# XS128.net
KiCad netlist of a schematic drawn in Altium Designer
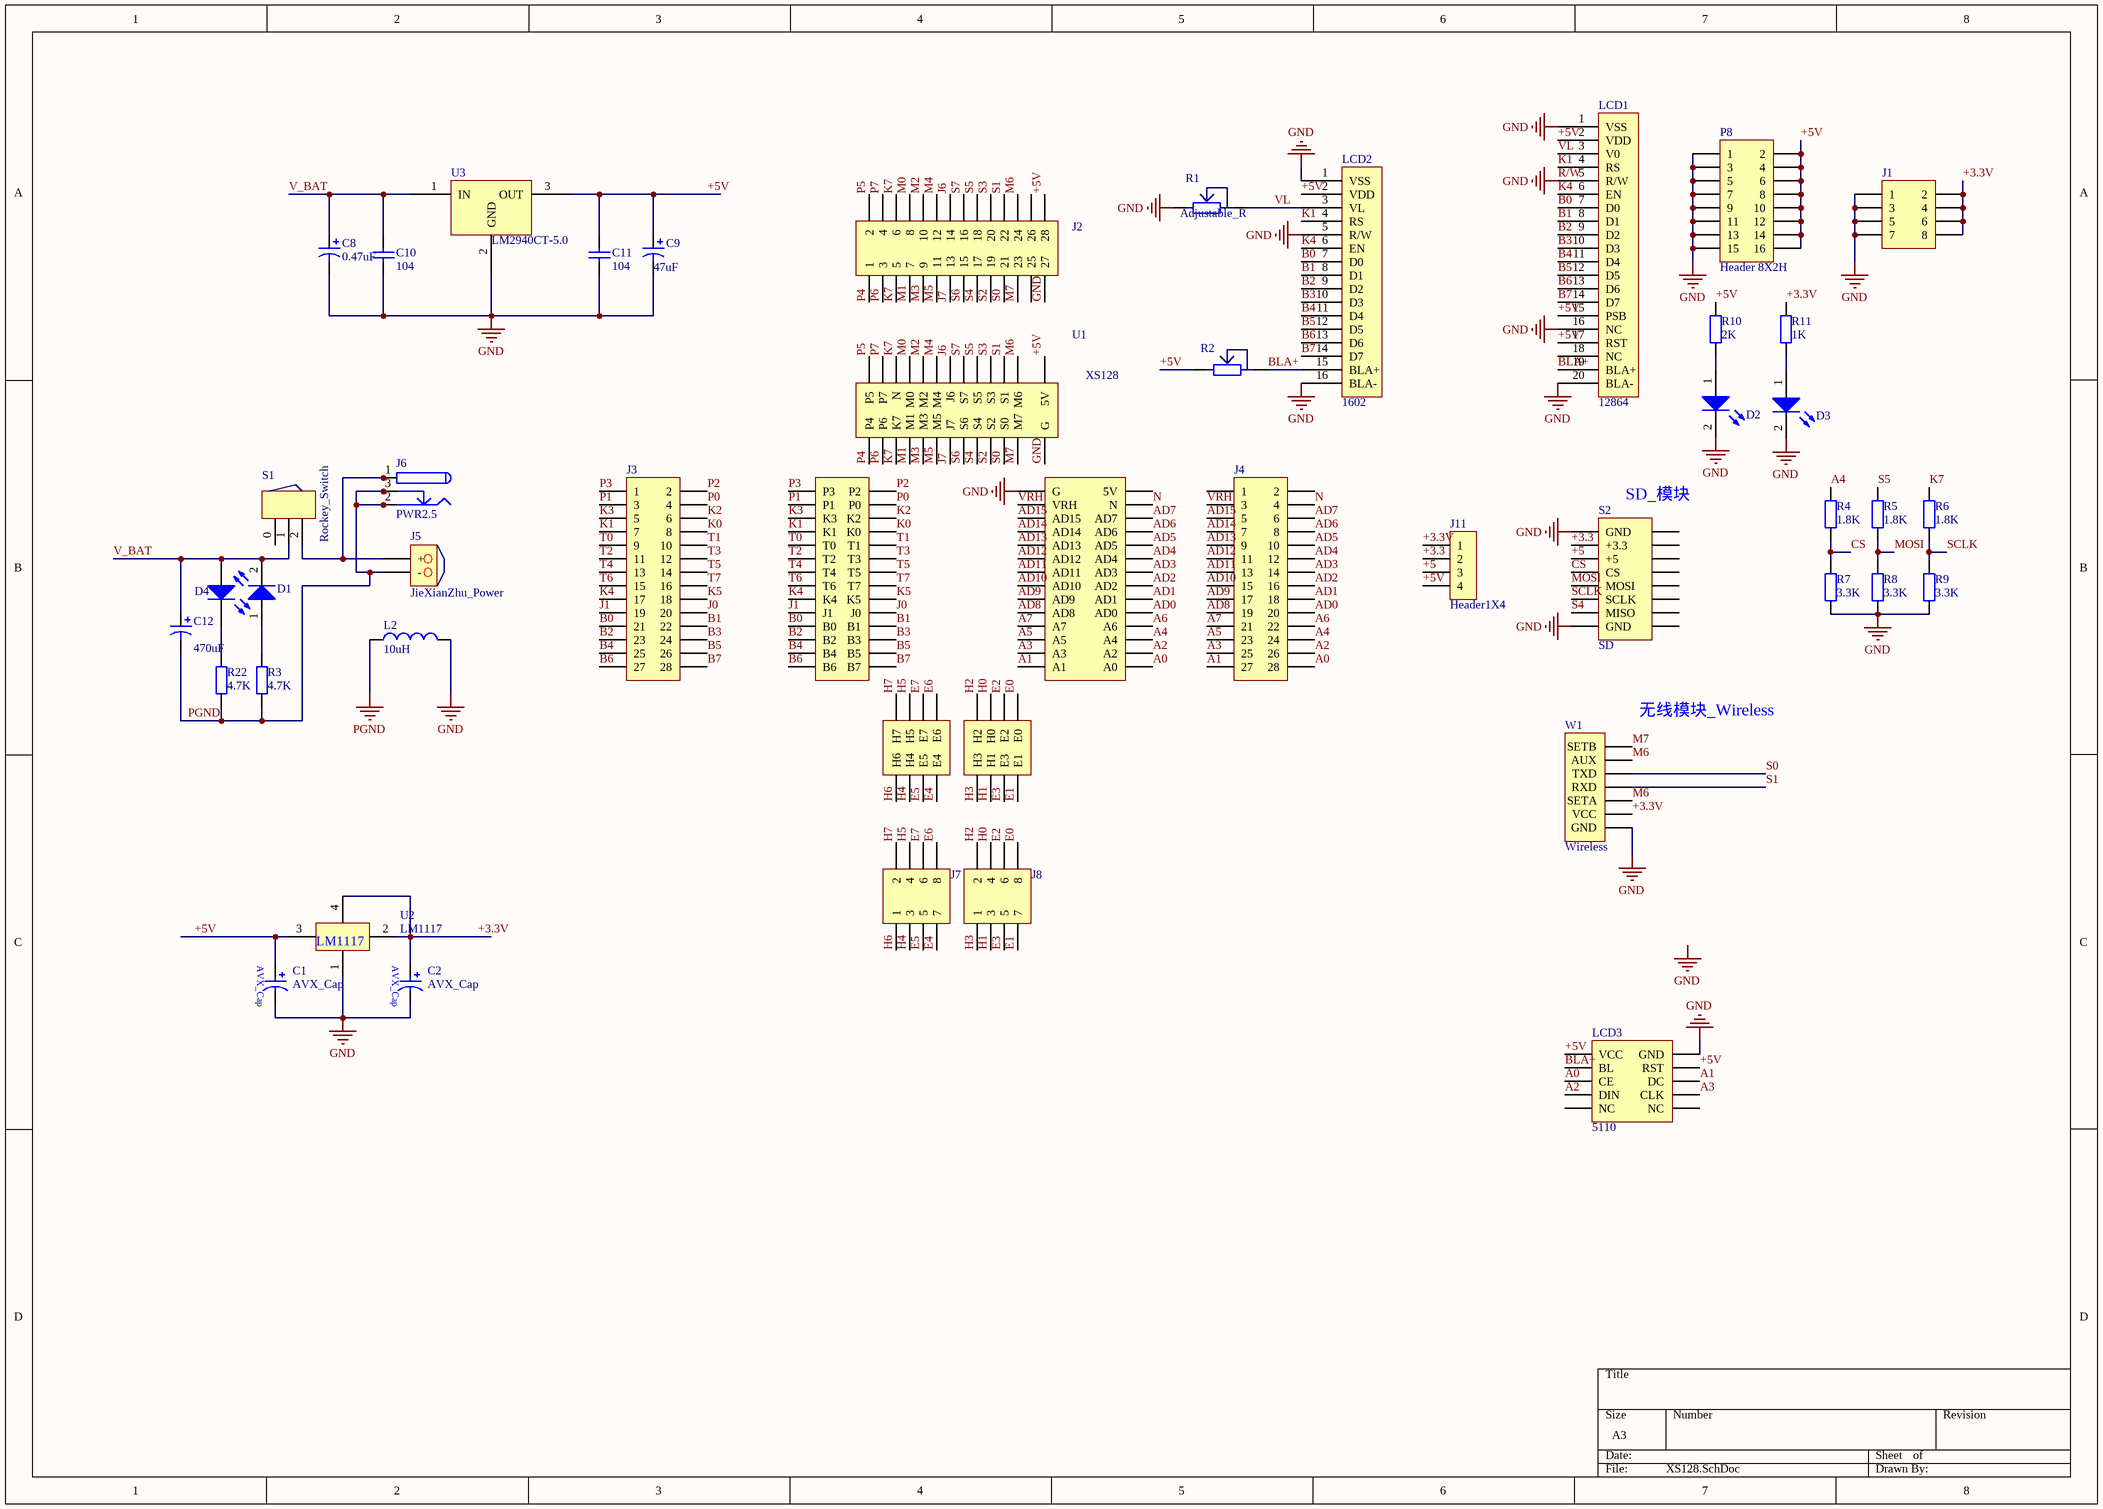
[diagram p0: XS128.SchDoc]

(export (version "E")
  (design (tool "Eeschema 10.0.6"))
  (components
    (comp (ref "C1") (value "AVX_Cap") (footprint "AVX_Cap_10uF") (libsource (lib "*") (part "AVX_Cap")))
    (comp (ref "C2") (value "AVX_Cap") (footprint "AVX_Cap_10uF") (libsource (lib "*") (part "AVX_Cap")))
    (comp (ref "C8")
      (value "0.47uF")
      (footprint "0.47UF/50V")
      (description "Polarized Capacitor (Surface Mount)")
      (fields (field (name "Comment") "Cap Pol3") (field (name "PUBLISHER") "Altium Limited"))
      (libsource (lib "元件库") (part "Cap Pol3"))
    )
    (comp (ref "C9")
      (value "47uF")
      (footprint "47uf/25V")
      (description "Polarized Capacitor (Surface Mount)")
      (fields (field (name "Comment") "Cap Pol3") (field (name "PUBLISHER") "Altium Limited"))
      (libsource (lib "元件库") (part "Cap Pol3"))
    )
    (comp (ref "C10")
      (value "104")
      (footprint "6-0805")
      (description "Capacitor")
      (fields (field (name "Comment") "Cap") (field (name "PUBLISHER") "Altium Limited"))
      (libsource (lib "元件库") (part "Cap"))
    )
    (comp (ref "C11")
      (value "104")
      (footprint "6-0805")
      (description "Capacitor")
      (fields (field (name "Comment") "Cap") (field (name "PUBLISHER") "Altium Limited"))
      (libsource (lib "元件库") (part "Cap"))
    )
    (comp (ref "C12")
      (value "470uF")
      (footprint "470uF/25V")
      (description "Polarized Capacitor (Radial)")
      (fields (field (name "Comment") "Cap Pol1") (field (name "PUBLISHER") "Altium Limited"))
      (libsource (lib "Miscellaneous Devices") (part "Cap Pol1"))
    )
    (comp (ref "D1")
      (value "LED1")
      (footprint "0805电阻贴片")
      (description "RED_LED")
      (fields (field (name "PUBLISHER") "Altium Limited"))
      (libsource (lib "") (part "LED1_1"))
    )
    (comp (ref "D2")
      (value "LED1")
      (footprint "0805电阻贴片")
      (description "RED_LED")
      (fields (field (name "PUBLISHER") "Altium Limited"))
      (libsource (lib "我的XS128集成库") (part "LED1"))
    )
    (comp (ref "D3")
      (value "LED1")
      (footprint "0805电阻贴片")
      (description "RED_LED")
      (fields (field (name "PUBLISHER") "Altium Limited"))
      (libsource (lib "我的XS128集成库") (part "LED1"))
    )
    (comp (ref "D4")
      (value "LED1")
      (footprint "3.2X1.6X1.1")
      (description "Typical RED GaAs LED")
      (fields (field (name "PUBLISHER") "Altium Limited"))
      (libsource (lib "Miscellaneous Devices") (part "LED1"))
    )
    (comp (ref "J1")
      (value "Header 4X2")
      (footprint "HDR2X4")
      (description "Header, 4-Pin, Dual row")
      (fields (field (name "PUBLISHER") "Altium Limited"))
      (libsource (lib "") (part "Header 4X2_1"))
    )
    (comp (ref "J2")
      (value "Header 14X2")
      (footprint "HDR2X14")
      (description "Header, 14-Pin, Dual row")
      (fields (field (name "PUBLISHER") "Altium Limited"))
      (libsource (lib "Miscellaneous Connectors") (part "Header 14X2"))
    )
    (comp (ref "J3")
      (value "Header 14X2")
      (footprint "HDR2X14")
      (description "Header, 14-Pin, Dual row")
      (fields (field (name "PUBLISHER") "Altium Limited"))
      (libsource (lib "") (part "Header 14X2_1"))
    )
    (comp (ref "J4")
      (value "Header 14X2")
      (footprint "HDR2X14")
      (description "Header, 14-Pin, Dual row")
      (fields (field (name "PUBLISHER") "Altium Limited"))
      (libsource (lib "") (part "Header 14X2_1"))
    )
    (comp (ref "J5")
      (value "JieXianZhu_Power")
      (footprint "jiexianzhu_power")
      (libsource (lib "*") (part "JieXianZhu_Power"))
    )
    (comp (ref "J6")
      (value "PWR2.5")
      (footprint "KLD-0202")
      (description "Low Voltage Power Supply Connector")
      (fields (field (name "PUBLISHER") "Altium Limited"))
      (libsource (lib "Miscellaneous Connectors") (part "PWR2.5"))
    )
    (comp (ref "J7")
      (value "Header 4X2")
      (footprint "HDR2X4")
      (description "Header, 4-Pin, Dual row")
      (fields (field (name "PUBLISHER") "Altium Limited"))
      (libsource (lib "Miscellaneous Connectors") (part "Header 4X2"))
    )
    (comp (ref "J8")
      (value "Header 4X2")
      (footprint "HDR2X4")
      (description "Header, 4-Pin, Dual row")
      (fields (field (name "PUBLISHER") "Altium Limited"))
      (libsource (lib "Miscellaneous Connectors") (part "Header 4X2"))
    )
    (comp (ref "J11") (value "Header1X4") (footprint "HDR1X4") (libsource (lib "*") (part "Header1X4")))
    (comp (ref "L2")
      (value "10uH")
      (footprint "INDUCTOR")
      (description "Inductor")
      (fields (field (name "PUBLISHER") "Altium Limited"))
      (libsource (lib "元件库") (part "Inductor"))
    )
    (comp (ref "LCD1") (value "12864") (footprint "HDR!X20") (libsource (lib "*") (part "12864")))
    (comp (ref "LCD2") (value "1602") (footprint "HDR1X16") (libsource (lib "*") (part "1602")))
    (comp (ref "LCD3") (value "5110") (footprint "5110") (libsource (lib "*") (part "5110")))
    (comp (ref "P8")
      (value "Header 8X2H")
      (footprint "HDR2X8H")
      (description "Header, 8-Pin, Dual row, Right Angle")
      (fields (field (name "PUBLISHER") "Altium Limited"))
      (libsource (lib "Miscellaneous Connectors") (part "Header 8X2H"))
    )
    (comp (ref "R1")
      (value "Adjustable_R")
      (footprint "Adjustable_R")
      (libsource (lib "*") (part "Adjustable_R"))
    )
    (comp (ref "R2")
      (value "Adjustable_R")
      (footprint "Adjustable_R")
      (libsource (lib "*") (part "Adjustable_R"))
    )
    (comp (ref "R3")
      (value "4.7K")
      (footprint "0805电阻贴片")
      (description "Resistor")
      (fields (field (name "Comment") "Res2") (field (name "PUBLISHER") "Altium Limited"))
      (libsource (lib "Miscellaneous Devices") (part "Res2"))
    )
    (comp (ref "R4")
      (value "1.8K")
      (footprint "0805电阻贴片")
      (description "Resistor")
      (fields (field (name "Comment") "Res2") (field (name "PUBLISHER") "Altium Limited"))
      (libsource (lib "我的XS128集成库") (part "Res2"))
    )
    (comp (ref "R5")
      (value "1.8K")
      (footprint "0805电阻贴片")
      (description "Resistor")
      (fields (field (name "Comment") "Res2") (field (name "PUBLISHER") "Altium Limited"))
      (libsource (lib "我的XS128集成库") (part "Res2"))
    )
    (comp (ref "R6")
      (value "1.8K")
      (footprint "0805电阻贴片")
      (description "Resistor")
      (fields (field (name "Comment") "Res2") (field (name "PUBLISHER") "Altium Limited"))
      (libsource (lib "我的XS128集成库") (part "Res2"))
    )
    (comp (ref "R7")
      (value "3.3K")
      (footprint "0805电阻贴片")
      (description "Resistor")
      (fields (field (name "Comment") "Res2") (field (name "PUBLISHER") "Altium Limited"))
      (libsource (lib "") (part "Res2_1"))
    )
    (comp (ref "R8")
      (value "3.3K")
      (footprint "0805电阻贴片")
      (description "Resistor")
      (fields (field (name "Comment") "Res2") (field (name "PUBLISHER") "Altium Limited"))
      (libsource (lib "") (part "Res2_1"))
    )
    (comp (ref "R9")
      (value "3.3K")
      (footprint "0805电阻贴片")
      (description "Resistor")
      (fields (field (name "Comment") "Res2") (field (name "PUBLISHER") "Altium Limited"))
      (libsource (lib "") (part "Res2_1"))
    )
    (comp (ref "R10")
      (value "2K")
      (footprint "0805电阻贴片")
      (description "Resistor")
      (fields (field (name "Comment") "Res2") (field (name "PUBLISHER") "Altium Limited"))
      (libsource (lib "我的XS128集成库") (part "Res2"))
    )
    (comp (ref "R11")
      (value "1K")
      (footprint "0805电阻贴片")
      (description "Resistor")
      (fields (field (name "Comment") "Res2") (field (name "PUBLISHER") "Altium Limited"))
      (libsource (lib "我的XS128集成库") (part "Res2"))
    )
    (comp (ref "R22")
      (value "4.7K")
      (footprint "2012[0805]")
      (description "Resistor")
      (fields (field (name "Comment") "Res2") (field (name "PUBLISHER") "Altium Limited"))
      (libsource (lib "Miscellaneous Devices") (part "Res2"))
    )
    (comp (ref "S1")
      (value "Rockey_Switch")
      (footprint "Rockey_Switch")
      (libsource (lib "*") (part "Rockey_Switch"))
    )
    (comp (ref "S2") (value "SD") (footprint "SD") (libsource (lib "*") (part "SD")))
    (comp (ref "U1") (value "XS128") (footprint "XS128接口") (libsource (lib "元件库") (part "XS128")))
    (comp (ref "U2") (value "LM1117") (footprint "SOT230LM1117") (libsource (lib "*") (part "LM1117")))
    (comp (ref "U3")
      (value "LM2940CT-5.0")
      (footprint "LM2940")
      (libsource (lib "元件库") (part "LM2940CT-5.0"))
    )
    (comp (ref "W1") (value "Wireless") (footprint "WIRELESS") (libsource (lib "*") (part "Wireless")))
  )
  (nets
    (net (code "1") (name "/+3.3") (class "Default")
      (node (ref "J11") (pin "2") (pinfunction "2_2") (pintype "passive"))
      (node (ref "S2") (pin "1") (pinfunction "+3.3_1") (pintype "passive"))
    )
    (net (code "2") (name "/+3.3V") (class "Default")
      (node (ref "C2") (pin "1") (pinfunction "+_1") (pintype "passive"))
      (node (ref "J1") (pin "2") (pinfunction "2_2") (pintype "passive"))
      (node (ref "J1") (pin "4") (pinfunction "4_4") (pintype "passive"))
      (node (ref "J1") (pin "6") (pinfunction "6_6") (pintype "passive"))
      (node (ref "J1") (pin "8") (pinfunction "8_8") (pintype "passive"))
      (node (ref "J11") (pin "1") (pinfunction "1_1") (pintype "passive"))
      (node (ref "R11") (pin "2") (pinfunction "2_2") (pintype "passive"))
      (node (ref "U2") (pin "2") (pinfunction "OUT_2") (pintype "passive"))
      (node (ref "U2") (pin "4") (pinfunction "TAB_4") (pintype "power_in"))
      (node (ref "W1") (pin "1") (pinfunction "VCC_1") (pintype "passive"))
    )
    (net (code "3") (name "/+5") (class "Default")
      (node (ref "J11") (pin "3") (pinfunction "3_3") (pintype "passive"))
      (node (ref "S2") (pin "2") (pinfunction "+5_2") (pintype "passive"))
    )
    (net (code "4") (name "/+5V") (class "Default")
      (node (ref "C1") (pin "1") (pinfunction "+_1") (pintype "passive"))
      (node (ref "C11") (pin "1") (pinfunction "1_1") (pintype "passive"))
      (node (ref "C9") (pin "1") (pinfunction "1_1") (pintype "passive"))
      (node (ref "J11") (pin "4") (pinfunction "4_4") (pintype "passive"))
      (node (ref "J2") (pin "28") (pinfunction "28_28") (pintype "passive"))
      (node (ref "LCD1") (pin "15") (pinfunction "PSB_15") (pintype "passive"))
      (node (ref "LCD1") (pin "17") (pinfunction "RST_17") (pintype "passive"))
      (node (ref "LCD1") (pin "2") (pinfunction "VDD_2") (pintype "passive"))
      (node (ref "LCD2") (pin "2") (pinfunction "VDD_2") (pintype "passive"))
      (node (ref "LCD3") (pin "0") (pinfunction "VCC_0") (pintype "passive"))
      (node (ref "LCD3") (pin "3") (pinfunction "RST_3") (pintype "passive"))
      (node (ref "P8") (pin "10") (pinfunction "10_10") (pintype "passive"))
      (node (ref "P8") (pin "12") (pinfunction "12_12") (pintype "passive"))
      (node (ref "P8") (pin "14") (pinfunction "14_14") (pintype "passive"))
      (node (ref "P8") (pin "16") (pinfunction "16_16") (pintype "passive"))
      (node (ref "P8") (pin "2") (pinfunction "2_2") (pintype "passive"))
      (node (ref "P8") (pin "4") (pinfunction "4_4") (pintype "passive"))
      (node (ref "P8") (pin "6") (pinfunction "6_6") (pintype "passive"))
      (node (ref "P8") (pin "8") (pinfunction "8_8") (pintype "passive"))
      (node (ref "R10") (pin "2") (pinfunction "2_2") (pintype "passive"))
      (node (ref "R2") (pin "1") (pinfunction "1_1") (pintype "passive"))
      (node (ref "U1") (pin "201") (pinfunction "5V_201") (pintype "passive"))
      (node (ref "U2") (pin "3") (pinfunction "IN_3") (pintype "passive"))
      (node (ref "U3") (pin "3") (pinfunction "OUT_3") (pintype "passive"))
    )
    (net (code "5") (name "/A0") (class "Default")
      (node (ref "J4") (pin "28") (pinfunction "28_28") (pintype "passive"))
      (node (ref "LCD3") (pin "4") (pinfunction "CE_4") (pintype "passive"))
      (node (ref "U1") (pin "301") (pinfunction "A0_301") (pintype "passive"))
    )
    (net (code "6") (name "/A1") (class "Default")
      (node (ref "J4") (pin "27") (pinfunction "27_27") (pintype "passive"))
      (node (ref "LCD3") (pin "5") (pinfunction "DC_5") (pintype "passive"))
      (node (ref "U1") (pin "302") (pinfunction "A1_302") (pintype "passive"))
    )
    (net (code "7") (name "/A2") (class "Default")
      (node (ref "J4") (pin "26") (pinfunction "26_26") (pintype "passive"))
      (node (ref "LCD3") (pin "6") (pinfunction "DIN_6") (pintype "passive"))
      (node (ref "U1") (pin "303") (pinfunction "A2_303") (pintype "passive"))
    )
    (net (code "8") (name "/A3") (class "Default")
      (node (ref "J4") (pin "25") (pinfunction "25_25") (pintype "passive"))
      (node (ref "LCD3") (pin "7") (pinfunction "CLK_7") (pintype "passive"))
      (node (ref "U1") (pin "304") (pinfunction "A3_304") (pintype "passive"))
    )
    (net (code "9") (name "/A4") (class "Default")
      (node (ref "J4") (pin "24") (pinfunction "24_24") (pintype "passive"))
      (node (ref "R4") (pin "2") (pinfunction "2_2") (pintype "passive"))
      (node (ref "U1") (pin "305") (pinfunction "A4_305") (pintype "passive"))
    )
    (net (code "10") (name "/A5") (class "Default")
      (node (ref "J4") (pin "23") (pinfunction "23_23") (pintype "passive"))
      (node (ref "U1") (pin "306") (pinfunction "A5_306") (pintype "passive"))
    )
    (net (code "11") (name "/A6") (class "Default")
      (node (ref "J4") (pin "22") (pinfunction "22_22") (pintype "passive"))
      (node (ref "U1") (pin "307") (pinfunction "A6_307") (pintype "passive"))
    )
    (net (code "12") (name "/A7") (class "Default")
      (node (ref "J4") (pin "21") (pinfunction "21_21") (pintype "passive"))
      (node (ref "U1") (pin "308") (pinfunction "A7_308") (pintype "passive"))
    )
    (net (code "13") (name "/AD0") (class "Default")
      (node (ref "J4") (pin "20") (pinfunction "20_20") (pintype "passive"))
      (node (ref "U1") (pin "309") (pinfunction "AD0_309") (pintype "passive"))
    )
    (net (code "14") (name "/AD1") (class "Default")
      (node (ref "J4") (pin "18") (pinfunction "18_18") (pintype "passive"))
      (node (ref "U1") (pin "311") (pinfunction "AD1_311") (pintype "passive"))
    )
    (net (code "15") (name "/AD2") (class "Default")
      (node (ref "J4") (pin "16") (pinfunction "16_16") (pintype "passive"))
      (node (ref "U1") (pin "313") (pinfunction "AD2_313") (pintype "passive"))
    )
    (net (code "16") (name "/AD3") (class "Default")
      (node (ref "J4") (pin "14") (pinfunction "14_14") (pintype "passive"))
      (node (ref "U1") (pin "315") (pinfunction "AD3_315") (pintype "passive"))
    )
    (net (code "17") (name "/AD4") (class "Default")
      (node (ref "J4") (pin "12") (pinfunction "12_12") (pintype "passive"))
      (node (ref "U1") (pin "317") (pinfunction "AD4_317") (pintype "passive"))
    )
    (net (code "18") (name "/AD5") (class "Default")
      (node (ref "J4") (pin "10") (pinfunction "10_10") (pintype "passive"))
      (node (ref "U1") (pin "319") (pinfunction "AD5_319") (pintype "passive"))
    )
    (net (code "19") (name "/AD6") (class "Default")
      (node (ref "J4") (pin "8") (pinfunction "8_8") (pintype "passive"))
      (node (ref "U1") (pin "321") (pinfunction "AD6_321") (pintype "passive"))
    )
    (net (code "20") (name "/AD7") (class "Default")
      (node (ref "J4") (pin "6") (pinfunction "6_6") (pintype "passive"))
      (node (ref "U1") (pin "323") (pinfunction "AD7_323") (pintype "passive"))
    )
    (net (code "21") (name "/AD8") (class "Default")
      (node (ref "J4") (pin "19") (pinfunction "19_19") (pintype "passive"))
      (node (ref "U1") (pin "310") (pinfunction "AD8_310") (pintype "passive"))
    )
    (net (code "22") (name "/AD9") (class "Default")
      (node (ref "J4") (pin "17") (pinfunction "17_17") (pintype "passive"))
      (node (ref "U1") (pin "312") (pinfunction "AD9_312") (pintype "passive"))
    )
    (net (code "23") (name "/AD10") (class "Default")
      (node (ref "J4") (pin "15") (pinfunction "15_15") (pintype "passive"))
      (node (ref "U1") (pin "314") (pinfunction "AD10_314") (pintype "passive"))
    )
    (net (code "24") (name "/AD11") (class "Default")
      (node (ref "J4") (pin "13") (pinfunction "13_13") (pintype "passive"))
      (node (ref "U1") (pin "316") (pinfunction "AD11_316") (pintype "passive"))
    )
    (net (code "25") (name "/AD12") (class "Default")
      (node (ref "J4") (pin "11") (pinfunction "11_11") (pintype "passive"))
      (node (ref "U1") (pin "318") (pinfunction "AD12_318") (pintype "passive"))
    )
    (net (code "26") (name "/AD13") (class "Default")
      (node (ref "J4") (pin "9") (pinfunction "9_9") (pintype "passive"))
      (node (ref "U1") (pin "320") (pinfunction "AD13_320") (pintype "passive"))
    )
    (net (code "27") (name "/AD14") (class "Default")
      (node (ref "J4") (pin "7") (pinfunction "7_7") (pintype "passive"))
      (node (ref "U1") (pin "322") (pinfunction "AD14_322") (pintype "passive"))
    )
    (net (code "28") (name "/AD15") (class "Default")
      (node (ref "J4") (pin "5") (pinfunction "5_5") (pintype "passive"))
      (node (ref "U1") (pin "324") (pinfunction "AD15_324") (pintype "passive"))
    )
    (net (code "29") (name "/B0") (class "Default")
      (node (ref "J3") (pin "21") (pinfunction "21_21") (pintype "passive"))
      (node (ref "LCD1") (pin "7") (pinfunction "D0_7") (pintype "passive"))
      (node (ref "LCD2") (pin "7") (pinfunction "D0_7") (pintype "passive"))
      (node (ref "U1") (pin "121") (pinfunction "B0_121") (pintype "passive"))
    )
    (net (code "30") (name "/B1") (class "Default")
      (node (ref "J3") (pin "22") (pinfunction "22_22") (pintype "passive"))
      (node (ref "LCD1") (pin "8") (pinfunction "D1_8") (pintype "passive"))
      (node (ref "LCD2") (pin "8") (pinfunction "D1_8") (pintype "passive"))
      (node (ref "U1") (pin "122") (pinfunction "B1_122") (pintype "passive"))
    )
    (net (code "31") (name "/B2") (class "Default")
      (node (ref "J3") (pin "23") (pinfunction "23_23") (pintype "passive"))
      (node (ref "LCD1") (pin "9") (pinfunction "D2_9") (pintype "passive"))
      (node (ref "LCD2") (pin "9") (pinfunction "D2_9") (pintype "passive"))
      (node (ref "U1") (pin "123") (pinfunction "B2_123") (pintype "passive"))
    )
    (net (code "32") (name "/B3") (class "Default")
      (node (ref "J3") (pin "24") (pinfunction "24_24") (pintype "passive"))
      (node (ref "LCD1") (pin "10") (pinfunction "D3_10") (pintype "passive"))
      (node (ref "LCD2") (pin "10") (pinfunction "D3_10") (pintype "passive"))
      (node (ref "U1") (pin "124") (pinfunction "B3_124") (pintype "passive"))
    )
    (net (code "33") (name "/B4") (class "Default")
      (node (ref "J3") (pin "25") (pinfunction "25_25") (pintype "passive"))
      (node (ref "LCD1") (pin "11") (pinfunction "D4_11") (pintype "passive"))
      (node (ref "LCD2") (pin "11") (pinfunction "D4_11") (pintype "passive"))
      (node (ref "U1") (pin "125") (pinfunction "B4_125") (pintype "passive"))
    )
    (net (code "34") (name "/B5") (class "Default")
      (node (ref "J3") (pin "26") (pinfunction "26_26") (pintype "passive"))
      (node (ref "LCD1") (pin "12") (pinfunction "D5_12") (pintype "passive"))
      (node (ref "LCD2") (pin "12") (pinfunction "D5_12") (pintype "passive"))
      (node (ref "U1") (pin "126") (pinfunction "B5_126") (pintype "passive"))
    )
    (net (code "35") (name "/B6") (class "Default")
      (node (ref "J3") (pin "27") (pinfunction "27_27") (pintype "passive"))
      (node (ref "LCD1") (pin "13") (pinfunction "D6_13") (pintype "passive"))
      (node (ref "LCD2") (pin "13") (pinfunction "D6_13") (pintype "passive"))
      (node (ref "U1") (pin "127") (pinfunction "B6_127") (pintype "passive"))
    )
    (net (code "36") (name "/B7") (class "Default")
      (node (ref "J3") (pin "28") (pinfunction "28_28") (pintype "passive"))
      (node (ref "LCD1") (pin "14") (pinfunction "D7_14") (pintype "passive"))
      (node (ref "LCD2") (pin "14") (pinfunction "D7_14") (pintype "passive"))
      (node (ref "U1") (pin "128") (pinfunction "B7_128") (pintype "passive"))
    )
    (net (code "37") (name "/BLA+") (class "Default")
      (node (ref "LCD1") (pin "19") (pinfunction "BLA+_19") (pintype "passive"))
      (node (ref "LCD2") (pin "15") (pinfunction "BLA+_15") (pintype "passive"))
      (node (ref "LCD3") (pin "2") (pinfunction "BL_2") (pintype "passive"))
      (node (ref "R2") (pin "2") (pinfunction "2_2") (pintype "passive"))
    )
    (net (code "38") (name "/CS") (class "Default")
      (node (ref "R4") (pin "1") (pinfunction "1_1") (pintype "passive"))
      (node (ref "R7") (pin "1") (pinfunction "1_1") (pintype "passive"))
      (node (ref "S2") (pin "3") (pinfunction "CS_3") (pintype "passive"))
    )
    (net (code "39") (name "/E0") (class "Default")
      (node (ref "J8") (pin "8") (pinfunction "8_8") (pintype "passive"))
      (node (ref "U1") (pin "508") (pinfunction "E0_508") (pintype "passive"))
    )
    (net (code "40") (name "/E1") (class "Default")
      (node (ref "J8") (pin "7") (pinfunction "7_7") (pintype "passive"))
      (node (ref "U1") (pin "507") (pinfunction "E1_507") (pintype "passive"))
    )
    (net (code "41") (name "/E2") (class "Default")
      (node (ref "J8") (pin "6") (pinfunction "6_6") (pintype "passive"))
      (node (ref "U1") (pin "506") (pinfunction "E2_506") (pintype "passive"))
    )
    (net (code "42") (name "/E3") (class "Default")
      (node (ref "J8") (pin "5") (pinfunction "5_5") (pintype "passive"))
      (node (ref "U1") (pin "505") (pinfunction "E3_505") (pintype "passive"))
    )
    (net (code "43") (name "/E4") (class "Default")
      (node (ref "J7") (pin "7") (pinfunction "7_7") (pintype "passive"))
      (node (ref "U1") (pin "407") (pinfunction "E4_407") (pintype "passive"))
    )
    (net (code "44") (name "/E5") (class "Default")
      (node (ref "J7") (pin "5") (pinfunction "5_5") (pintype "passive"))
      (node (ref "U1") (pin "405") (pinfunction "E5_405") (pintype "passive"))
    )
    (net (code "45") (name "/E6") (class "Default")
      (node (ref "J7") (pin "8") (pinfunction "8_8") (pintype "passive"))
      (node (ref "U1") (pin "408") (pinfunction "E6_408") (pintype "passive"))
    )
    (net (code "46") (name "/E7") (class "Default")
      (node (ref "J7") (pin "6") (pinfunction "6_6") (pintype "passive"))
      (node (ref "U1") (pin "406") (pinfunction "E7_406") (pintype "passive"))
    )
    (net (code "47") (name "/H0") (class "Default")
      (node (ref "J8") (pin "4") (pinfunction "4_4") (pintype "passive"))
      (node (ref "U1") (pin "504") (pinfunction "H0_504") (pintype "passive"))
    )
    (net (code "48") (name "/H1") (class "Default")
      (node (ref "J8") (pin "3") (pinfunction "3_3") (pintype "passive"))
      (node (ref "U1") (pin "503") (pinfunction "H1_503") (pintype "passive"))
    )
    (net (code "49") (name "/H2") (class "Default")
      (node (ref "J8") (pin "2") (pinfunction "2_2") (pintype "passive"))
      (node (ref "U1") (pin "502") (pinfunction "H2_502") (pintype "passive"))
    )
    (net (code "50") (name "/H3") (class "Default")
      (node (ref "J8") (pin "1") (pinfunction "1_1") (pintype "passive"))
      (node (ref "U1") (pin "501") (pinfunction "H3_501") (pintype "passive"))
    )
    (net (code "51") (name "/H4") (class "Default")
      (node (ref "J7") (pin "3") (pinfunction "3_3") (pintype "passive"))
      (node (ref "U1") (pin "403") (pinfunction "H4_403") (pintype "passive"))
    )
    (net (code "52") (name "/H5") (class "Default")
      (node (ref "J7") (pin "4") (pinfunction "4_4") (pintype "passive"))
      (node (ref "U1") (pin "404") (pinfunction "H5_404") (pintype "passive"))
    )
    (net (code "53") (name "/H6") (class "Default")
      (node (ref "J7") (pin "1") (pinfunction "1_1") (pintype "passive"))
      (node (ref "U1") (pin "401") (pinfunction "H6_401") (pintype "passive"))
    )
    (net (code "54") (name "/H7") (class "Default")
      (node (ref "J7") (pin "2") (pinfunction "2_2") (pintype "passive"))
      (node (ref "U1") (pin "402") (pinfunction "H7_402") (pintype "passive"))
    )
    (net (code "55") (name "/J0") (class "Default")
      (node (ref "J3") (pin "20") (pinfunction "20_20") (pintype "passive"))
      (node (ref "U1") (pin "120") (pinfunction "J0_120") (pintype "passive"))
    )
    (net (code "56") (name "/J1") (class "Default")
      (node (ref "J3") (pin "19") (pinfunction "19_19") (pintype "passive"))
      (node (ref "U1") (pin "119") (pinfunction "J1_119") (pintype "passive"))
    )
    (net (code "57") (name "/J6") (class "Default")
      (node (ref "J2") (pin "14") (pinfunction "14_14") (pintype "passive"))
      (node (ref "U1") (pin "215") (pinfunction "J6_215") (pintype "passive"))
    )
    (net (code "58") (name "/J7") (class "Default")
      (node (ref "J2") (pin "13") (pinfunction "13_13") (pintype "passive"))
      (node (ref "U1") (pin "216") (pinfunction "J7_216") (pintype "passive"))
    )
    (net (code "59") (name "/K0") (class "Default")
      (node (ref "J3") (pin "8") (pinfunction "8_8") (pintype "passive"))
      (node (ref "U1") (pin "108") (pinfunction "K0_108") (pintype "passive"))
    )
    (net (code "60") (name "/K1") (class "Default")
      (node (ref "J3") (pin "7") (pinfunction "7_7") (pintype "passive"))
      (node (ref "LCD1") (pin "4") (pinfunction "RS_4") (pintype "passive"))
      (node (ref "LCD2") (pin "4") (pinfunction "RS_4") (pintype "passive"))
      (node (ref "U1") (pin "107") (pinfunction "K1_107") (pintype "passive"))
    )
    (net (code "61") (name "/K2") (class "Default")
      (node (ref "J3") (pin "6") (pinfunction "6_6") (pintype "passive"))
      (node (ref "U1") (pin "106") (pinfunction "K2_106") (pintype "passive"))
    )
    (net (code "62") (name "/K3") (class "Default")
      (node (ref "J3") (pin "5") (pinfunction "5_5") (pintype "passive"))
      (node (ref "U1") (pin "105") (pinfunction "K3_105") (pintype "passive"))
    )
    (net (code "63") (name "/K4") (class "Default")
      (node (ref "J3") (pin "17") (pinfunction "17_17") (pintype "passive"))
      (node (ref "LCD1") (pin "6") (pinfunction "EN_6") (pintype "passive"))
      (node (ref "LCD2") (pin "6") (pinfunction "EN_6") (pintype "passive"))
      (node (ref "U1") (pin "117") (pinfunction "K4_117") (pintype "passive"))
    )
    (net (code "64") (name "/K5") (class "Default")
      (node (ref "J3") (pin "18") (pinfunction "18_18") (pintype "passive"))
      (node (ref "U1") (pin "118") (pinfunction "K5_118") (pintype "passive"))
    )
    (net (code "65") (name "/K7") (class "Default")
      (node (ref "J2") (pin "5") (pinfunction "5_5") (pintype "passive"))
      (node (ref "J2") (pin "6") (pinfunction "6_6") (pintype "passive"))
      (node (ref "R6") (pin "2") (pinfunction "2_2") (pintype "passive"))
      (node (ref "U1") (pin "223") (pinfunction "N_223") (pintype "power_in"))
      (node (ref "U1") (pin "224") (pinfunction "K7_224") (pintype "passive"))
    )
    (net (code "66") (name "/M0") (class "Default")
      (node (ref "J2") (pin "8") (pinfunction "8_8") (pintype "passive"))
      (node (ref "U1") (pin "221") (pinfunction "M0_221") (pintype "passive"))
    )
    (net (code "67") (name "/M1") (class "Default")
      (node (ref "J2") (pin "7") (pinfunction "7_7") (pintype "passive"))
      (node (ref "U1") (pin "222") (pinfunction "M1_222") (pintype "passive"))
    )
    (net (code "68") (name "/M2") (class "Default")
      (node (ref "J2") (pin "10") (pinfunction "10_10") (pintype "passive"))
      (node (ref "U1") (pin "219") (pinfunction "M2_219") (pintype "passive"))
    )
    (net (code "69") (name "/M3") (class "Default")
      (node (ref "J2") (pin "9") (pinfunction "9_9") (pintype "passive"))
      (node (ref "U1") (pin "220") (pinfunction "M3_220") (pintype "passive"))
    )
    (net (code "70") (name "/M4") (class "Default")
      (node (ref "J2") (pin "12") (pinfunction "12_12") (pintype "passive"))
      (node (ref "U1") (pin "217") (pinfunction "M4_217") (pintype "passive"))
    )
    (net (code "71") (name "/M5") (class "Default")
      (node (ref "J2") (pin "11") (pinfunction "11_11") (pintype "passive"))
      (node (ref "U1") (pin "218") (pinfunction "M5_218") (pintype "passive"))
    )
    (net (code "72") (name "/M6") (class "Default")
      (node (ref "J2") (pin "24") (pinfunction "24_24") (pintype "passive"))
      (node (ref "U1") (pin "205") (pinfunction "M6_205") (pintype "passive"))
      (node (ref "W1") (pin "2") (pinfunction "SETA_2") (pintype "passive"))
      (node (ref "W1") (pin "5") (pinfunction "AUX_5") (pintype "passive"))
    )
    (net (code "73") (name "/M7") (class "Default")
      (node (ref "J2") (pin "23") (pinfunction "23_23") (pintype "passive"))
      (node (ref "U1") (pin "206") (pinfunction "M7_206") (pintype "passive"))
      (node (ref "W1") (pin "6") (pinfunction "SETB_6") (pintype "passive"))
    )
    (net (code "74") (name "/MOSI") (class "Default")
      (node (ref "R5") (pin "1") (pinfunction "1_1") (pintype "passive"))
      (node (ref "R8") (pin "1") (pinfunction "1_1") (pintype "passive"))
      (node (ref "S2") (pin "4") (pinfunction "MOSI_4") (pintype "passive"))
    )
    (net (code "75") (name "/N") (class "Default")
      (node (ref "J4") (pin "4") (pinfunction "4_4") (pintype "passive"))
      (node (ref "U1") (pin "325") (pinfunction "N_325") (pintype "power_in"))
    )
    (net (code "76") (name "/P0") (class "Default")
      (node (ref "J3") (pin "4") (pinfunction "4_4") (pintype "passive"))
      (node (ref "U1") (pin "104") (pinfunction "P0_104") (pintype "passive"))
    )
    (net (code "77") (name "/P1") (class "Default")
      (node (ref "J3") (pin "3") (pinfunction "3_3") (pintype "passive"))
      (node (ref "U1") (pin "103") (pinfunction "P1_103") (pintype "passive"))
    )
    (net (code "78") (name "/P2") (class "Default")
      (node (ref "J3") (pin "2") (pinfunction "2_2") (pintype "passive"))
      (node (ref "U1") (pin "102") (pinfunction "P2_102") (pintype "passive"))
    )
    (net (code "79") (name "/P3") (class "Default")
      (node (ref "J3") (pin "1") (pinfunction "1_1") (pintype "passive"))
      (node (ref "U1") (pin "101") (pinfunction "P3_101") (pintype "passive"))
    )
    (net (code "80") (name "/P4") (class "Default")
      (node (ref "J2") (pin "1") (pinfunction "1_1") (pintype "passive"))
      (node (ref "U1") (pin "228") (pinfunction "P4_228") (pintype "passive"))
    )
    (net (code "81") (name "/P5") (class "Default")
      (node (ref "J2") (pin "2") (pinfunction "2_2") (pintype "passive"))
      (node (ref "U1") (pin "227") (pinfunction "P5_227") (pintype "passive"))
    )
    (net (code "82") (name "/P6") (class "Default")
      (node (ref "J2") (pin "3") (pinfunction "3_3") (pintype "passive"))
      (node (ref "U1") (pin "226") (pinfunction "P6_226") (pintype "passive"))
    )
    (net (code "83") (name "/P7") (class "Default")
      (node (ref "J2") (pin "4") (pinfunction "4_4") (pintype "passive"))
      (node (ref "U1") (pin "225") (pinfunction "P7_225") (pintype "passive"))
    )
    (net (code "84") (name "/S0") (class "Default")
      (node (ref "J2") (pin "21") (pinfunction "21_21") (pintype "passive"))
      (node (ref "U1") (pin "208") (pinfunction "S0_208") (pintype "passive"))
      (node (ref "W1") (pin "4") (pinfunction "TXD_4") (pintype "passive"))
    )
    (net (code "85") (name "/S1") (class "Default")
      (node (ref "J2") (pin "22") (pinfunction "22_22") (pintype "passive"))
      (node (ref "U1") (pin "207") (pinfunction "S1_207") (pintype "passive"))
      (node (ref "W1") (pin "3") (pinfunction "RXD_3") (pintype "passive"))
    )
    (net (code "86") (name "/S2") (class "Default")
      (node (ref "J2") (pin "19") (pinfunction "19_19") (pintype "passive"))
      (node (ref "U1") (pin "210") (pinfunction "S2_210") (pintype "passive"))
    )
    (net (code "87") (name "/S3") (class "Default")
      (node (ref "J2") (pin "20") (pinfunction "20_20") (pintype "passive"))
      (node (ref "U1") (pin "209") (pinfunction "S3_209") (pintype "passive"))
    )
    (net (code "88") (name "/S4") (class "Default")
      (node (ref "J2") (pin "17") (pinfunction "17_17") (pintype "passive"))
      (node (ref "S2") (pin "6") (pinfunction "MISO_6") (pintype "passive"))
      (node (ref "U1") (pin "212") (pinfunction "S4_212") (pintype "passive"))
    )
    (net (code "89") (name "/S5") (class "Default")
      (node (ref "J2") (pin "18") (pinfunction "18_18") (pintype "passive"))
      (node (ref "R5") (pin "2") (pinfunction "2_2") (pintype "passive"))
      (node (ref "U1") (pin "211") (pinfunction "S5_211") (pintype "passive"))
    )
    (net (code "90") (name "/S6") (class "Default")
      (node (ref "J2") (pin "15") (pinfunction "15_15") (pintype "passive"))
      (node (ref "U1") (pin "214") (pinfunction "S6_214") (pintype "passive"))
    )
    (net (code "91") (name "/S7") (class "Default")
      (node (ref "J2") (pin "16") (pinfunction "16_16") (pintype "passive"))
      (node (ref "U1") (pin "213") (pinfunction "S7_213") (pintype "passive"))
    )
    (net (code "92") (name "/SCLK") (class "Default")
      (node (ref "R6") (pin "1") (pinfunction "1_1") (pintype "passive"))
      (node (ref "R9") (pin "1") (pinfunction "1_1") (pintype "passive"))
      (node (ref "S2") (pin "5") (pinfunction "SCLK_5") (pintype "passive"))
    )
    (net (code "93") (name "/T0") (class "Default")
      (node (ref "J3") (pin "9") (pinfunction "9_9") (pintype "passive"))
      (node (ref "U1") (pin "109") (pinfunction "T0_109") (pintype "passive"))
    )
    (net (code "94") (name "/T1") (class "Default")
      (node (ref "J3") (pin "10") (pinfunction "10_10") (pintype "passive"))
      (node (ref "U1") (pin "110") (pinfunction "T1_110") (pintype "passive"))
    )
    (net (code "95") (name "/T2") (class "Default")
      (node (ref "J3") (pin "11") (pinfunction "11_11") (pintype "passive"))
      (node (ref "U1") (pin "111") (pinfunction "T2_111") (pintype "passive"))
    )
    (net (code "96") (name "/T3") (class "Default")
      (node (ref "J3") (pin "12") (pinfunction "12_12") (pintype "passive"))
      (node (ref "U1") (pin "112") (pinfunction "T3_112") (pintype "passive"))
    )
    (net (code "97") (name "/T4") (class "Default")
      (node (ref "J3") (pin "13") (pinfunction "13_13") (pintype "passive"))
      (node (ref "U1") (pin "113") (pinfunction "T4_113") (pintype "passive"))
    )
    (net (code "98") (name "/T5") (class "Default")
      (node (ref "J3") (pin "14") (pinfunction "14_14") (pintype "passive"))
      (node (ref "U1") (pin "114") (pinfunction "T5_114") (pintype "passive"))
    )
    (net (code "99") (name "/T6") (class "Default")
      (node (ref "J3") (pin "15") (pinfunction "15_15") (pintype "passive"))
      (node (ref "U1") (pin "115") (pinfunction "T6_115") (pintype "passive"))
    )
    (net (code "100") (name "/T7") (class "Default")
      (node (ref "J3") (pin "16") (pinfunction "16_16") (pintype "passive"))
      (node (ref "U1") (pin "116") (pinfunction "T7_116") (pintype "passive"))
    )
    (net (code "101") (name "/VL") (class "Default")
      (node (ref "LCD1") (pin "3") (pinfunction "V0_3") (pintype "passive"))
      (node (ref "LCD2") (pin "3") (pinfunction "VL_3") (pintype "passive"))
      (node (ref "R1") (pin "2") (pinfunction "2_2") (pintype "passive"))
    )
    (net (code "102") (name "/VRH") (class "Default")
      (node (ref "J4") (pin "3") (pinfunction "3_3") (pintype "passive"))
      (node (ref "U1") (pin "326") (pinfunction "VRH_326") (pintype "passive"))
    )
    (net (code "103") (name "/V_BAT") (class "Default")
      (node (ref "C10") (pin "1") (pinfunction "1_1") (pintype "passive"))
      (node (ref "C12") (pin "1") (pinfunction "1_1") (pintype "passive"))
      (node (ref "C8") (pin "1") (pinfunction "1_1") (pintype "passive"))
      (node (ref "D1") (pin "2") (pinfunction "K_2") (pintype "passive"))
      (node (ref "D4") (pin "1") (pinfunction "A_1") (pintype "passive"))
      (node (ref "S1") (pin "1") (pinfunction "B_1") (pintype "power_in"))
      (node (ref "U3") (pin "1") (pinfunction "IN_1") (pintype "passive"))
    )
    (net (code "104") (name "GND") (class "Default")
      (node (ref "C1") (pin "2") (pinfunction "-_2") (pintype "passive"))
      (node (ref "C10") (pin "2") (pinfunction "2_2") (pintype "passive"))
      (node (ref "C11") (pin "2") (pinfunction "2_2") (pintype "passive"))
      (node (ref "C2") (pin "2") (pinfunction "-_2") (pintype "passive"))
      (node (ref "C8") (pin "2") (pinfunction "2_2") (pintype "passive"))
      (node (ref "C9") (pin "2") (pinfunction "2_2") (pintype "passive"))
      (node (ref "D2") (pin "2") (pinfunction "K_2") (pintype "passive"))
      (node (ref "D3") (pin "2") (pinfunction "K_2") (pintype "passive"))
      (node (ref "J1") (pin "1") (pinfunction "1_1") (pintype "passive"))
      (node (ref "J1") (pin "3") (pinfunction "3_3") (pintype "passive"))
      (node (ref "J1") (pin "5") (pinfunction "5_5") (pintype "passive"))
      (node (ref "J1") (pin "7") (pinfunction "7_7") (pintype "passive"))
      (node (ref "J2") (pin "27") (pinfunction "27_27") (pintype "passive"))
      (node (ref "L2") (pin "2") (pinfunction "2_2") (pintype "passive"))
      (node (ref "LCD1") (pin "1") (pinfunction "VSS_1") (pintype "passive"))
      (node (ref "LCD1") (pin "16") (pinfunction "NC_16") (pintype "passive"))
      (node (ref "LCD1") (pin "20") (pinfunction "BLA-_20") (pintype "passive"))
      (node (ref "LCD1") (pin "5") (pinfunction "R/W_5") (pintype "passive"))
      (node (ref "LCD2") (pin "1") (pinfunction "VSS_1") (pintype "passive"))
      (node (ref "LCD2") (pin "16") (pinfunction "BLA-_16") (pintype "passive"))
      (node (ref "LCD2") (pin "5") (pinfunction "R/W_5") (pintype "passive"))
      (node (ref "LCD3") (pin "1") (pinfunction "GND_1") (pintype "passive"))
      (node (ref "P8") (pin "1") (pinfunction "1_1") (pintype "passive"))
      (node (ref "P8") (pin "11") (pinfunction "11_11") (pintype "passive"))
      (node (ref "P8") (pin "13") (pinfunction "13_13") (pintype "passive"))
      (node (ref "P8") (pin "15") (pinfunction "15_15") (pintype "passive"))
      (node (ref "P8") (pin "3") (pinfunction "3_3") (pintype "passive"))
      (node (ref "P8") (pin "5") (pinfunction "5_5") (pintype "passive"))
      (node (ref "P8") (pin "7") (pinfunction "7_7") (pintype "passive"))
      (node (ref "P8") (pin "9") (pinfunction "9_9") (pintype "passive"))
      (node (ref "R1") (pin "1") (pinfunction "1_1") (pintype "passive"))
      (node (ref "R7") (pin "2") (pinfunction "2_2") (pintype "passive"))
      (node (ref "R8") (pin "2") (pinfunction "2_2") (pintype "passive"))
      (node (ref "R9") (pin "2") (pinfunction "2_2") (pintype "passive"))
      (node (ref "S2") (pin "0") (pinfunction "GND_0") (pintype "passive"))
      (node (ref "S2") (pin "7") (pinfunction "GND_7") (pintype "passive"))
      (node (ref "U1") (pin "202") (pinfunction "G_202") (pintype "passive"))
      (node (ref "U1") (pin "328") (pinfunction "G_328") (pintype "passive"))
      (node (ref "U2") (pin "1") (pinfunction "GND_1") (pintype "power_in"))
      (node (ref "U3") (pin "2") (pinfunction "GND_2") (pintype "passive"))
      (node (ref "W1") (pin "0") (pinfunction "GND_0") (pintype "passive"))
    )
    (net (code "105") (name "Net-(D1-A)") (class "Default")
      (node (ref "D1") (pin "1") (pinfunction "A_1") (pintype "passive"))
      (node (ref "R3") (pin "2") (pinfunction "2_2") (pintype "passive"))
    )
    (net (code "106") (name "Net-(D2-A)") (class "Default")
      (node (ref "D2") (pin "1") (pinfunction "A_1") (pintype "passive"))
      (node (ref "R10") (pin "1") (pinfunction "1_1") (pintype "passive"))
    )
    (net (code "107") (name "Net-(D3-A)") (class "Default")
      (node (ref "D3") (pin "1") (pinfunction "A_1") (pintype "passive"))
      (node (ref "R11") (pin "1") (pinfunction "1_1") (pintype "passive"))
    )
    (net (code "108") (name "Net-(D4-K)") (class "Default")
      (node (ref "D4") (pin "2") (pinfunction "K_2") (pintype "passive"))
      (node (ref "R22") (pin "2") (pinfunction "2_2") (pintype "passive"))
    )
    (net (code "109") (name "Net-(J5-+)") (class "Default")
      (node (ref "J5") (pin "0") (pinfunction "+_0") (pintype "passive"))
      (node (ref "J6") (pin "1") (pinfunction "1_1") (pintype "power_in"))
      (node (ref "J6") (pin "1A") (pinfunction "1A_1A") (pintype "power_in"))
      (node (ref "J6") (pin "1B") (pinfunction "1B_1B") (pintype "power_in"))
      (node (ref "S1") (pin "2") (pinfunction "C_2") (pintype "power_in"))
    )
    (net (code "110") (name "PGND") (class "Default")
      (node (ref "C12") (pin "2") (pinfunction "2_2") (pintype "passive"))
      (node (ref "J5") (pin "1") (pinfunction "-_1") (pintype "passive"))
      (node (ref "J6") (pin "2") (pinfunction "2_2") (pintype "power_in"))
      (node (ref "J6") (pin "2A") (pinfunction "2A_2A") (pintype "power_in"))
      (node (ref "J6") (pin "2B") (pinfunction "2B_2B") (pintype "power_in"))
      (node (ref "J6") (pin "3") (pinfunction "3_3") (pintype "power_in"))
      (node (ref "J6") (pin "3A") (pinfunction "3A_3A") (pintype "power_in"))
      (node (ref "J6") (pin "3B") (pinfunction "3B_3B") (pintype "power_in"))
      (node (ref "L2") (pin "1") (pinfunction "1_1") (pintype "passive"))
      (node (ref "R22") (pin "1") (pinfunction "1_1") (pintype "passive"))
      (node (ref "R3") (pin "1") (pinfunction "1_1") (pintype "passive"))
    )
    (net (code "111") (name "unconnected-(J2-Pad25)") (class "Default")
      (node (ref "J2") (pin "25") (pinfunction "25_25") (pintype "passive"))
    )
    (net (code "112") (name "unconnected-(J2-Pad26)") (class "Default")
      (node (ref "J2") (pin "26") (pinfunction "26_26") (pintype "passive"))
    )
    (net (code "113") (name "unconnected-(J4-Pad1)") (class "Default")
      (node (ref "J4") (pin "1") (pinfunction "1_1") (pintype "passive"))
    )
    (net (code "114") (name "unconnected-(J4-Pad2)") (class "Default")
      (node (ref "J4") (pin "2") (pinfunction "2_2") (pintype "passive"))
    )
    (net (code "115") (name "unconnected-(LCD1-NC-Pad18)") (class "Default")
      (node (ref "LCD1") (pin "18") (pinfunction "NC_18") (pintype "passive"))
    )
    (net (code "116") (name "unconnected-(LCD3-NC-Pad8)") (class "Default")
      (node (ref "LCD3") (pin "8") (pinfunction "NC_8") (pintype "passive"))
    )
    (net (code "117") (name "unconnected-(LCD3-NC-Pad9)") (class "Default")
      (node (ref "LCD3") (pin "9") (pinfunction "NC_9") (pintype "passive"))
    )
    (net (code "118") (name "unconnected-(S1-A-Pad0)") (class "Default")
      (node (ref "S1") (pin "0") (pinfunction "A_0") (pintype "power_in"))
    )
    (net (code "119") (name "unconnected-(S2-Pad8)") (class "Default")
      (node (ref "S2") (pin "8") (pinfunction "8_8") (pintype "passive"))
    )
    (net (code "120") (name "unconnected-(S2-Pad9)") (class "Default")
      (node (ref "S2") (pin "9") (pinfunction "9_9") (pintype "passive"))
    )
    (net (code "121") (name "unconnected-(S2-Pad10)") (class "Default")
      (node (ref "S2") (pin "10") (pinfunction "10_10") (pintype "passive"))
    )
    (net (code "122") (name "unconnected-(S2-Pad11)") (class "Default")
      (node (ref "S2") (pin "11") (pinfunction "11_11") (pintype "passive"))
    )
    (net (code "123") (name "unconnected-(S2-Pad12)") (class "Default")
      (node (ref "S2") (pin "12") (pinfunction "12_12") (pintype "passive"))
    )
    (net (code "124") (name "unconnected-(S2-Pad13)") (class "Default")
      (node (ref "S2") (pin "13") (pinfunction "13_13") (pintype "passive"))
    )
    (net (code "125") (name "unconnected-(S2-Pad14)") (class "Default")
      (node (ref "S2") (pin "14") (pinfunction "14_14") (pintype "passive"))
    )
    (net (code "126") (name "unconnected-(S2-Pad15)") (class "Default")
      (node (ref "S2") (pin "15") (pinfunction "15_15") (pintype "passive"))
    )
    (net (code "127") (name "unconnected-(U1-5V-Pad327)") (class "Default")
      (node (ref "U1") (pin "327") (pinfunction "5V_327") (pintype "passive"))
    )
  )
)
